# STM32.net
KiCad netlist of a schematic drawn in Altium Designer
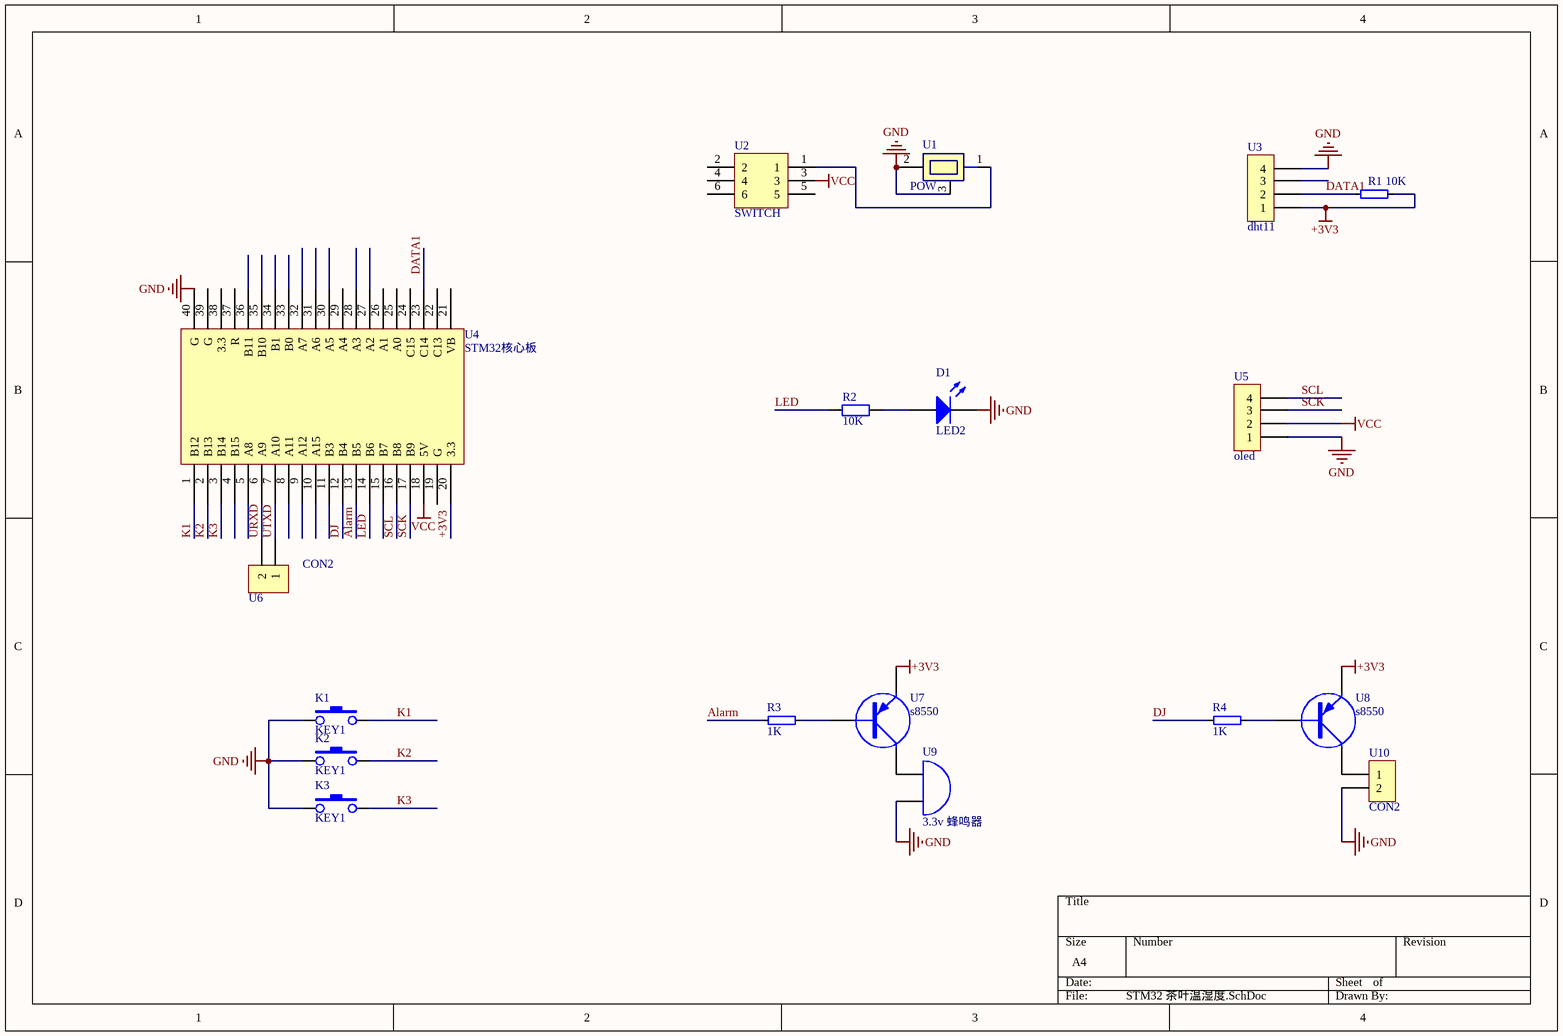
[diagram p0: STM32 茶叶温湿度.SchDoc]

(export (version "E")
  (design (tool "Eeschema 10.0.6"))
  (components
    (comp (ref "D1")
      (value "LED2")
      (footprint "LED")
      (description "Typical RED, GREEN, YELLOW, AMBER GaAs LED")
      (fields (field (name "PUBLISHER") "Altium Limited"))
      (libsource (lib "Miscellaneous Devices") (part "LED2"))
    )
    (comp (ref "K1") (value "KEY1") (footprint "KEY1") (libsource (lib "Singlechip-51") (part "KEY1")))
    (comp (ref "K2") (value "KEY1") (footprint "KEY1") (libsource (lib "Singlechip-51") (part "KEY1")))
    (comp (ref "K3") (value "KEY1") (footprint "KEY1") (libsource (lib "Singlechip-51") (part "KEY1")))
    (comp (ref "R1") (value "10K") (footprint "R-DIP") (libsource (lib "51SCH") (part "10K")))
    (comp (ref "R2")
      (value "10K")
      (footprint "R-DIP")
      (description "Resistor")
      (fields (field (name "Comment") "1K") (field (name "PUBLISHER") "Altium Limited"))
      (libsource (lib "Miscellaneous Devices") (part "Res2"))
    )
    (comp (ref "R3") (value "1K") (footprint "R-DIP") (libsource (lib "51SCH") (part "1K")))
    (comp (ref "R4") (value "1K") (footprint "R-DIP") (libsource (lib "51SCH") (part "1K")))
    (comp (ref "U1") (value "POW") (footprint "DCM") (libsource (lib "51SCH") (part "POW")))
    (comp (ref "U2") (value "SWITCH") (footprint "KG1") (libsource (lib "51SCH") (part "SWITCH")))
    (comp (ref "U3") (value "dht11") (footprint "HDR1X4") (libsource (lib "51SCH") (part "CON4")))
    (comp (ref "U4") (value "STM32核心板") (footprint "STC") (libsource (lib "Singlechip-51") (part "STM32核心板")))
    (comp (ref "U5") (value "oled") (footprint "HDR1X4") (libsource (lib "51SCH") (part "CON4")))
    (comp (ref "U6") (value "CON2") (footprint "SIP2") (libsource (lib "51SCH") (part "CON2")))
    (comp (ref "U7") (value "s8550") (footprint "PNP") (libsource (lib "51SCH") (part "PNP")))
    (comp (ref "U8") (value "s8550") (footprint "PNP") (libsource (lib "51SCH") (part "PNP")))
    (comp (ref "U9") (value "3.3v 蜂鸣器") (footprint "BEEP") (libsource (lib "51SCH") (part "BELL")))
    (comp (ref "U10") (value "CON2") (footprint "SIP2") (libsource (lib "") (part "CON2_1")))
  )
  (nets
    (net (code "1") (name "+3V3") (class "Default")
      (node (ref "R1") (pin "1") (pinfunction "1_1") (pintype "passive"))
      (node (ref "U3") (pin "1") (pinfunction "1_1") (pintype "passive"))
      (node (ref "U4") (pin "20") (pinfunction "3.3_20") (pintype "passive"))
      (node (ref "U7") (pin "2") (pinfunction "E_2") (pintype "passive"))
      (node (ref "U8") (pin "2") (pinfunction "E_2") (pintype "passive"))
    )
    (net (code "2") (name "/Alarm") (class "Default")
      (node (ref "R3") (pin "1") (pinfunction "1_1") (pintype "passive"))
      (node (ref "U4") (pin "13") (pinfunction "B5_13") (pintype "passive"))
    )
    (net (code "3") (name "/DATA1") (class "Default")
      (node (ref "R1") (pin "2") (pinfunction "2_2") (pintype "passive"))
      (node (ref "U3") (pin "2") (pinfunction "2_2") (pintype "passive"))
      (node (ref "U4") (pin "23") (pinfunction "C14_23") (pintype "passive"))
    )
    (net (code "4") (name "/DJ") (class "Default")
      (node (ref "R4") (pin "1") (pinfunction "1_1") (pintype "passive"))
      (node (ref "U4") (pin "12") (pinfunction "B4_12") (pintype "passive"))
    )
    (net (code "5") (name "/K1") (class "Default")
      (node (ref "K1") (pin "2") (pinfunction "10_2") (pintype "passive"))
      (node (ref "U4") (pin "1") (pinfunction "B12_1") (pintype "passive"))
    )
    (net (code "6") (name "/K2") (class "Default")
      (node (ref "K2") (pin "2") (pinfunction "10_2") (pintype "passive"))
      (node (ref "U4") (pin "2") (pinfunction "B13_2") (pintype "passive"))
    )
    (net (code "7") (name "/K3") (class "Default")
      (node (ref "K3") (pin "2") (pinfunction "10_2") (pintype "passive"))
      (node (ref "U4") (pin "3") (pinfunction "B14_3") (pintype "passive"))
    )
    (net (code "8") (name "/LED") (class "Default")
      (node (ref "R2") (pin "2") (pinfunction "2_2") (pintype "passive"))
      (node (ref "U4") (pin "14") (pinfunction "B6_14") (pintype "passive"))
    )
    (net (code "9") (name "/SCK") (class "Default")
      (node (ref "U4") (pin "17") (pinfunction "B9_17") (pintype "passive"))
      (node (ref "U5") (pin "3") (pinfunction "3_3") (pintype "passive"))
    )
    (net (code "10") (name "/SCL") (class "Default")
      (node (ref "U4") (pin "16") (pinfunction "B8_16") (pintype "passive"))
      (node (ref "U5") (pin "4") (pinfunction "4_4") (pintype "passive"))
    )
    (net (code "11") (name "/URXD") (class "Default")
      (node (ref "U4") (pin "6") (pinfunction "A9_6") (pintype "passive"))
      (node (ref "U6") (pin "2") (pinfunction "2_2") (pintype "passive"))
    )
    (net (code "12") (name "/UTXD") (class "Default")
      (node (ref "U4") (pin "7") (pinfunction "A10_7") (pintype "passive"))
      (node (ref "U6") (pin "1") (pinfunction "1_1") (pintype "passive"))
    )
    (net (code "13") (name "GND") (class "Default")
      (node (ref "D1") (pin "2") (pinfunction "K_2") (pintype "passive"))
      (node (ref "K1") (pin "1") (pinfunction "1_1") (pintype "passive"))
      (node (ref "K2") (pin "1") (pinfunction "1_1") (pintype "passive"))
      (node (ref "K3") (pin "1") (pinfunction "1_1") (pintype "passive"))
      (node (ref "U1") (pin "2") (pintype "passive"))
      (node (ref "U1") (pin "3") (pintype "passive"))
      (node (ref "U10") (pin "2") (pinfunction "2_2") (pintype "passive"))
      (node (ref "U3") (pin "4") (pinfunction "4_4") (pintype "passive"))
      (node (ref "U4") (pin "40") (pinfunction "G_40") (pintype "passive"))
      (node (ref "U5") (pin "1") (pinfunction "1_1") (pintype "passive"))
      (node (ref "U9") (pin "2") (pinfunction "B_2") (pintype "passive"))
    )
    (net (code "14") (name "Net-(D1-A)") (class "Default")
      (node (ref "D1") (pin "1") (pinfunction "A_1") (pintype "passive"))
      (node (ref "R2") (pin "1") (pinfunction "1_1") (pintype "passive"))
    )
    (net (code "15") (name "Net-(U1-Pad1)") (class "Default")
      (node (ref "U1") (pin "1") (pintype "passive"))
      (node (ref "U2") (pin "1") (pinfunction "1_1") (pintype "passive"))
    )
    (net (code "16") (name "Net-(U7-B)") (class "Default")
      (node (ref "R3") (pin "2") (pinfunction "2_2") (pintype "passive"))
      (node (ref "U7") (pin "1") (pinfunction "B_1") (pintype "passive"))
    )
    (net (code "17") (name "Net-(U7-C)") (class "Default")
      (node (ref "U7") (pin "3") (pinfunction "C_3") (pintype "passive"))
      (node (ref "U9") (pin "1") (pinfunction "A_1") (pintype "passive"))
    )
    (net (code "18") (name "Net-(U8-B)") (class "Default")
      (node (ref "R4") (pin "2") (pinfunction "2_2") (pintype "passive"))
      (node (ref "U8") (pin "1") (pinfunction "B_1") (pintype "passive"))
    )
    (net (code "19") (name "Net-(U8-C)") (class "Default")
      (node (ref "U10") (pin "1") (pinfunction "1_1") (pintype "passive"))
      (node (ref "U8") (pin "3") (pinfunction "C_3") (pintype "passive"))
    )
    (net (code "20") (name "VCC") (class "Default")
      (node (ref "U2") (pin "3") (pinfunction "3_3") (pintype "passive"))
      (node (ref "U4") (pin "18") (pinfunction "5V_18") (pintype "passive"))
      (node (ref "U5") (pin "2") (pinfunction "2_2") (pintype "passive"))
    )
    (net (code "21") (name "unconnected-(U2-Pad2)") (class "Default")
      (node (ref "U2") (pin "2") (pinfunction "2_2") (pintype "passive"))
    )
    (net (code "22") (name "unconnected-(U2-Pad4)") (class "Default")
      (node (ref "U2") (pin "4") (pinfunction "4_4") (pintype "passive"))
    )
    (net (code "23") (name "unconnected-(U2-Pad5)") (class "Default")
      (node (ref "U2") (pin "5") (pinfunction "5_5") (pintype "passive"))
    )
    (net (code "24") (name "unconnected-(U2-Pad6)") (class "Default")
      (node (ref "U2") (pin "6") (pinfunction "6_6") (pintype "passive"))
    )
    (net (code "25") (name "unconnected-(U3-Pad3)") (class "Default")
      (node (ref "U3") (pin "3") (pinfunction "3_3") (pintype "passive"))
    )
    (net (code "26") (name "unconnected-(U4-3.3-Pad38)") (class "Default")
      (node (ref "U4") (pin "38") (pinfunction "3.3_38") (pintype "passive"))
    )
    (net (code "27") (name "unconnected-(U4-A0-Pad25)") (class "Default")
      (node (ref "U4") (pin "25") (pinfunction "A0_25") (pintype "passive"))
    )
    (net (code "28") (name "unconnected-(U4-A1-Pad26)") (class "Default")
      (node (ref "U4") (pin "26") (pinfunction "A1_26") (pintype "passive"))
    )
    (net (code "29") (name "unconnected-(U4-A2-Pad27)") (class "Default")
      (node (ref "U4") (pin "27") (pinfunction "A2_27") (pintype "passive"))
    )
    (net (code "30") (name "unconnected-(U4-A3-Pad28)") (class "Default")
      (node (ref "U4") (pin "28") (pinfunction "A3_28") (pintype "passive"))
    )
    (net (code "31") (name "unconnected-(U4-A4-Pad29)") (class "Default")
      (node (ref "U4") (pin "29") (pinfunction "A4_29") (pintype "passive"))
    )
    (net (code "32") (name "unconnected-(U4-A5-Pad30)") (class "Default")
      (node (ref "U4") (pin "30") (pinfunction "A5_30") (pintype "passive"))
    )
    (net (code "33") (name "unconnected-(U4-A6-Pad31)") (class "Default")
      (node (ref "U4") (pin "31") (pinfunction "A6_31") (pintype "passive"))
    )
    (net (code "34") (name "unconnected-(U4-A7-Pad32)") (class "Default")
      (node (ref "U4") (pin "32") (pinfunction "A7_32") (pintype "passive"))
    )
    (net (code "35") (name "unconnected-(U4-A8-Pad5)") (class "Default")
      (node (ref "U4") (pin "5") (pinfunction "A8_5") (pintype "passive"))
    )
    (net (code "36") (name "unconnected-(U4-A11-Pad8)") (class "Default")
      (node (ref "U4") (pin "8") (pinfunction "A11_8") (pintype "passive"))
    )
    (net (code "37") (name "unconnected-(U4-A12-Pad9)") (class "Default")
      (node (ref "U4") (pin "9") (pinfunction "A12_9") (pintype "passive"))
    )
    (net (code "38") (name "unconnected-(U4-A15-Pad10)") (class "Default")
      (node (ref "U4") (pin "10") (pinfunction "A15_10") (pintype "passive"))
    )
    (net (code "39") (name "unconnected-(U4-B0-Pad33)") (class "Default")
      (node (ref "U4") (pin "33") (pinfunction "B0_33") (pintype "passive"))
    )
    (net (code "40") (name "unconnected-(U4-B1-Pad34)") (class "Default")
      (node (ref "U4") (pin "34") (pinfunction "B1_34") (pintype "passive"))
    )
    (net (code "41") (name "unconnected-(U4-B3-Pad11)") (class "Default")
      (node (ref "U4") (pin "11") (pinfunction "B3_11") (pintype "passive"))
    )
    (net (code "42") (name "unconnected-(U4-B7-Pad15)") (class "Default")
      (node (ref "U4") (pin "15") (pinfunction "B7_15") (pintype "passive"))
    )
    (net (code "43") (name "unconnected-(U4-B10-Pad35)") (class "Default")
      (node (ref "U4") (pin "35") (pinfunction "B10_35") (pintype "passive"))
    )
    (net (code "44") (name "unconnected-(U4-B11-Pad36)") (class "Default")
      (node (ref "U4") (pin "36") (pinfunction "B11_36") (pintype "passive"))
    )
    (net (code "45") (name "unconnected-(U4-B15-Pad4)") (class "Default")
      (node (ref "U4") (pin "4") (pinfunction "B15_4") (pintype "passive"))
    )
    (net (code "46") (name "unconnected-(U4-C13-Pad22)") (class "Default")
      (node (ref "U4") (pin "22") (pinfunction "C13_22") (pintype "passive"))
    )
    (net (code "47") (name "unconnected-(U4-C15-Pad24)") (class "Default")
      (node (ref "U4") (pin "24") (pinfunction "C15_24") (pintype "passive"))
    )
    (net (code "48") (name "unconnected-(U4-G-Pad19)") (class "Default")
      (node (ref "U4") (pin "19") (pinfunction "G_19") (pintype "passive"))
    )
    (net (code "49") (name "unconnected-(U4-G-Pad39)") (class "Default")
      (node (ref "U4") (pin "39") (pinfunction "G_39") (pintype "passive"))
    )
    (net (code "50") (name "unconnected-(U4-R-Pad37)") (class "Default")
      (node (ref "U4") (pin "37") (pinfunction "R_37") (pintype "passive"))
    )
    (net (code "51") (name "unconnected-(U4-VB-Pad21)") (class "Default")
      (node (ref "U4") (pin "21") (pinfunction "VB_21") (pintype "passive"))
    )
  )
)
